# BG95_RF.net
KiCad netlist of a schematic drawn in Altium Designer
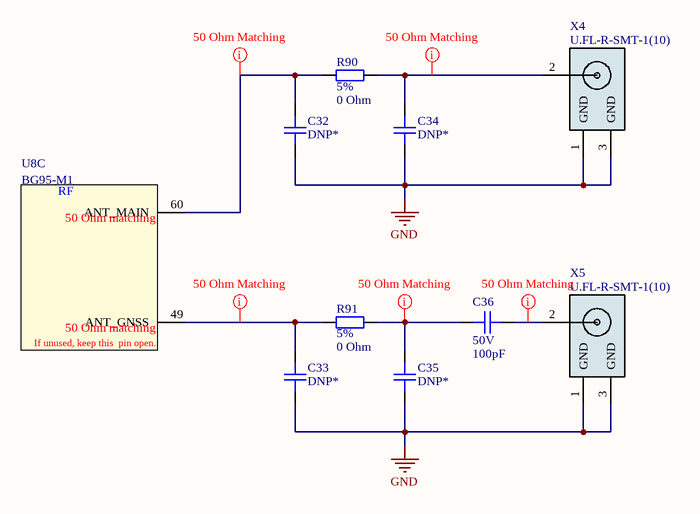
[diagram p0: BG95_RF.SchDoc]

(export (version "E")
  (design (tool "Eeschema 10.0.6"))
  (components
    (comp (ref "C32")
      (value "DNP*")
      (footprint "C0402")
      (description "Placeholder for a 0402 capacitor")
      (libsource (lib "capacitors_smd") (part "CAP CER NO_BOM 0402"))
    )
    (comp (ref "C33")
      (value "DNP*")
      (footprint "C0402")
      (description "Placeholder for a 0402 capacitor")
      (libsource (lib "capacitors_smd") (part "CAP CER NO_BOM 0402"))
    )
    (comp (ref "C34")
      (value "DNP*")
      (footprint "C0402")
      (description "Placeholder for a 0402 capacitor")
      (libsource (lib "capacitors_smd") (part "CAP CER NO_BOM 0402"))
    )
    (comp (ref "C35")
      (value "DNP*")
      (footprint "C0402")
      (description "Placeholder for a 0402 capacitor")
      (libsource (lib "capacitors_smd") (part "CAP CER NO_BOM 0402"))
    )
    (comp (ref "C36")
      (value "C 100pF 50V C0G, NP0 0402")
      (footprint "C0402")
      (description "100pF ±5% 50V Ceramic Capacitor C0G, NP0 0402 (1005 Metric)")
      (fields
        (field (name "MANUFACTURER") "Yageo")
        (field (name "MANUFACTURER PART NUMBER") "CC0402JRNPO9BN101")
        (field (name "VOLTAGE") "50V")
        (field (name "CAPACITANCE") "100pF")
      )
      (libsource (lib "capacitors_smd") (part "C 100pF 50V C0G, NP0 0402"))
    )
    (comp (ref "R90")
      (value "RES SMD 0 OHM JUMPER 1/16W 0402")
      (footprint "R0402")
      (description "0 Ohms Jumper 0.063W, 1/16W Chip Resistor 0402 (1005 Metric) Moisture Resistant Thick Film")
      (fields
        (field (name "MANUFACTURER") "Yageo")
        (field (name "MANUFACTURER PART NUMBER") "RC0402JR-070RL")
        (field (name "TOLERANCE") "5%")
        (field (name "RESISTANCE") "0 Ohm")
      )
      (libsource (lib "resistors_smd") (part "RES SMD 0 OHM JUMPER 1/16W 0402"))
    )
    (comp (ref "R91")
      (value "RES SMD 0 OHM JUMPER 1/16W 0402")
      (footprint "R0402")
      (description "0 Ohms Jumper 0.063W, 1/16W Chip Resistor 0402 (1005 Metric) Moisture Resistant Thick Film")
      (fields
        (field (name "MANUFACTURER") "Yageo")
        (field (name "MANUFACTURER PART NUMBER") "RC0402JR-070RL")
        (field (name "TOLERANCE") "5%")
        (field (name "RESISTANCE") "0 Ohm")
      )
      (libsource (lib "resistors_smd") (part "RES SMD 0 OHM JUMPER 1/16W 0402"))
    )
    (comp (ref "U8")
      (value "BG95-M1")
      (footprint "BG95")
      (description "LTE Cat M1, LTE Cat NB2 and EGPRS Transceiver Module Antenna Not Included Surface Mount")
      (fields (field (name "MANUFACTURER") "QUECTEL"))
      (libsource (lib "BLDC_Motor_Driver") (part "MOD BG95 RX TXRX CELLULAR LTE/NAV SMD"))
    )
    (comp (ref "X4")
      (value "U.FL-R-SMT-1(10)")
      (footprint "CONN U.FL RCPT STR 50 OHM SMD")
      (description "U.FL (UMCC) Connector Receptacle, Male Pin 50Ohm Surface Mount Solder")
      (fields (field (name "MANUFACTURER") "Hirose"))
      (libsource (lib "RelibondHMI") (part "CONN U.FL RCPT STR 50 OHM SMD"))
    )
    (comp (ref "X5")
      (value "U.FL-R-SMT-1(10)")
      (footprint "CONN U.FL RCPT STR 50 OHM SMD")
      (description "U.FL (UMCC) Connector Receptacle, Male Pin 50Ohm Surface Mount Solder")
      (fields (field (name "MANUFACTURER") "Hirose"))
      (libsource (lib "RelibondHMI") (part "CONN U.FL RCPT STR 50 OHM SMD"))
    )
  )
  (nets
    (net (code "1") (name "GND") (class "Default")
      (node (ref "C32") (pin "1") (pinfunction "1_1") (pintype "passive"))
      (node (ref "C33") (pin "1") (pinfunction "1_1") (pintype "passive"))
      (node (ref "C34") (pin "1") (pinfunction "1_1") (pintype "passive"))
      (node (ref "C35") (pin "1") (pinfunction "1_1") (pintype "passive"))
      (node (ref "X4") (pin "1") (pinfunction "GND_1") (pintype "passive"))
      (node (ref "X4") (pin "3") (pinfunction "GND_3") (pintype "passive"))
      (node (ref "X5") (pin "1") (pinfunction "GND_1") (pintype "passive"))
      (node (ref "X5") (pin "3") (pinfunction "GND_3") (pintype "passive"))
    )
    (net (code "2") (name "Net-(C35-Pad2)") (class "Default")
      (node (ref "C35") (pin "2") (pinfunction "2_2") (pintype "passive"))
      (node (ref "C36") (pin "1") (pinfunction "1_1") (pintype "passive"))
      (node (ref "R91") (pin "2") (pinfunction "2_2") (pintype "passive"))
    )
    (net (code "3") (name "Net-(U8C-ANT_GNSS)") (class "Default")
      (node (ref "C33") (pin "2") (pinfunction "2_2") (pintype "passive"))
      (node (ref "R91") (pin "1") (pinfunction "1_1") (pintype "passive"))
      (node (ref "U8") (pin "49") (pinfunction "ANT_GNSS_49") (pintype "passive"))
    )
    (net (code "4") (name "Net-(U8C-ANT_MAIN)") (class "Default")
      (node (ref "C32") (pin "2") (pinfunction "2_2") (pintype "passive"))
      (node (ref "R90") (pin "1") (pinfunction "1_1") (pintype "passive"))
      (node (ref "U8") (pin "60") (pinfunction "ANT_MAIN_60") (pintype "passive"))
    )
    (net (code "5") (name "Net-(X4-Signal)") (class "Default")
      (node (ref "C34") (pin "2") (pinfunction "2_2") (pintype "passive"))
      (node (ref "R90") (pin "2") (pinfunction "2_2") (pintype "passive"))
      (node (ref "X4") (pin "2") (pinfunction "Signal_2") (pintype "passive"))
    )
    (net (code "6") (name "Net-(X5-Signal)") (class "Default")
      (node (ref "C36") (pin "2") (pinfunction "2_2") (pintype "passive"))
      (node (ref "X5") (pin "2") (pinfunction "Signal_2") (pintype "passive"))
    )
  )
)
